# Overview.net
KiCad netlist of a schematic drawn in Altium Designer
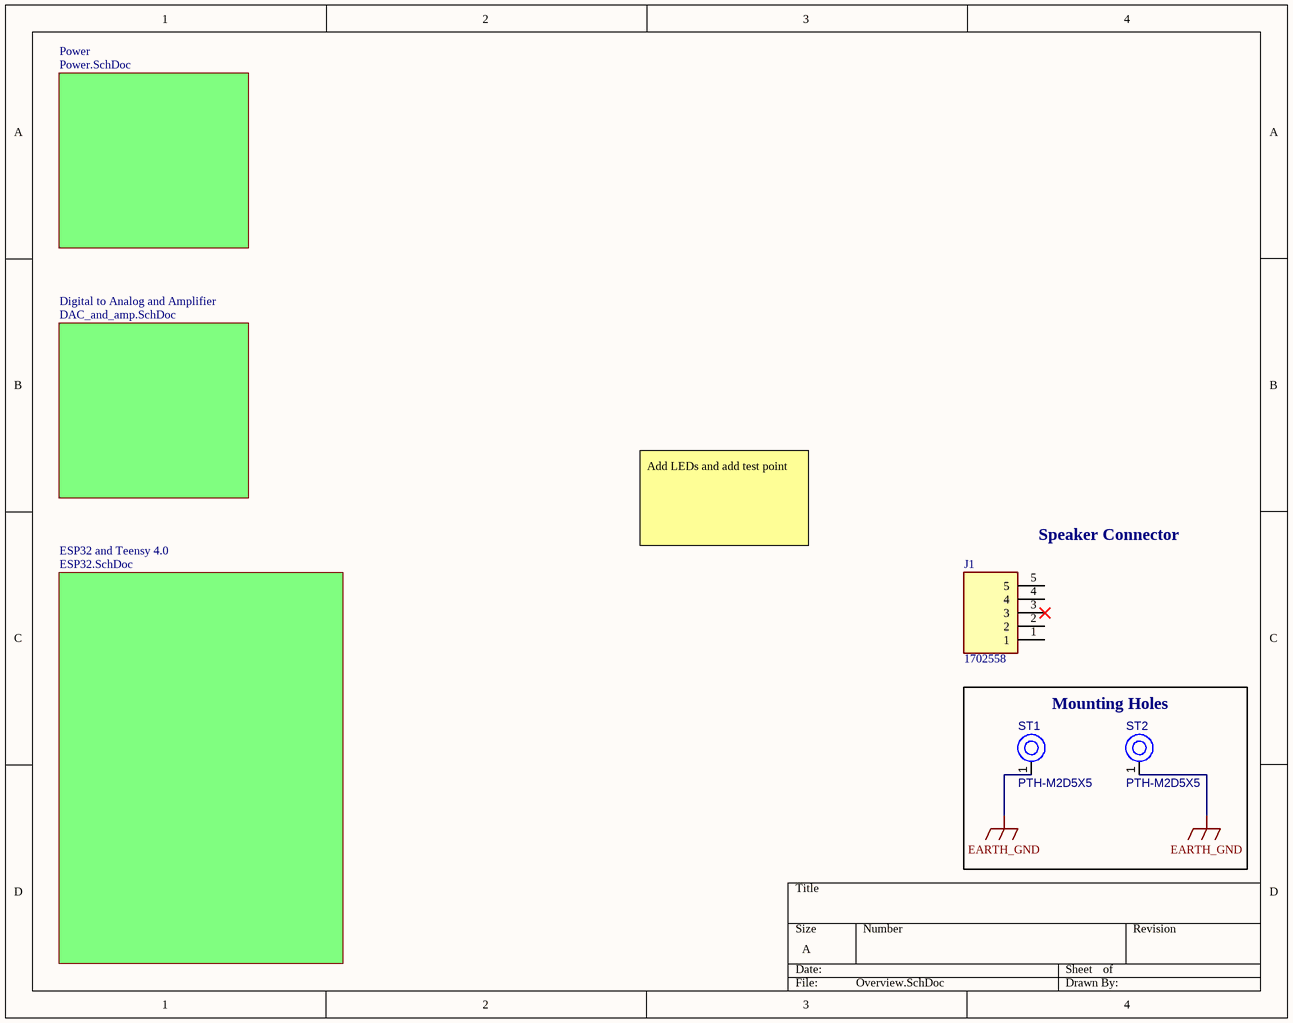
[diagram p0: Overview.SchDoc]

(export (version "E")
  (design (tool "Eeschema 10.0.6"))
  (components
    (comp (ref "J1")
      (value "1702558")
      (footprint "SamacSys:1702558")
      (description "Connector")
      (fields (field (name "MOUSER PART NUMBER") "651-1702558"))
      (libsource (lib "*") (part "1702558"))
    )
    (comp (ref "ST1")
      (value "PTH-M2D5X5")
      (footprint "PTH-M2D5X5")
      (description "M2 PTH (2.5mm), 5mm pad")
      (libsource (lib "Spartan Racing Altium Workspace") (part "CMP-00028-00000-1"))
    )
    (comp (ref "ST2")
      (value "PTH-M2D5X5")
      (footprint "PTH-M2D5X5")
      (description "M2 PTH (2.5mm), 5mm pad")
      (libsource (lib "Spartan Racing Altium Workspace") (part "CMP-00028-00000-1"))
    )
  )
  (nets
    (net (code "1") (name "EARTH_GND") (class "Default")
      (node (ref "ST1") (pin "1") (pinfunction "H1_1") (pintype "passive"))
      (node (ref "ST2") (pin "1") (pinfunction "H1_1") (pintype "passive"))
    )
    (net (code "2") (name "unconnected-(J1-Pad1)") (class "Default")
      (node (ref "J1") (pin "1") (pinfunction "1_1") (pintype "passive"))
    )
    (net (code "3") (name "unconnected-(J1-Pad2)") (class "Default")
      (node (ref "J1") (pin "2") (pinfunction "2_2") (pintype "passive"))
    )
    (net (code "4") (name "unconnected-(J1-Pad3)") (class "Default")
      (node (ref "J1") (pin "3") (pinfunction "3_3") (pintype "passive+no_connect"))
    )
    (net (code "5") (name "unconnected-(J1-Pad4)") (class "Default")
      (node (ref "J1") (pin "4") (pinfunction "4_4") (pintype "passive"))
    )
    (net (code "6") (name "unconnected-(J1-Pad5)") (class "Default")
      (node (ref "J1") (pin "5") (pinfunction "5_5") (pintype "passive"))
    )
  )
)
